# 7-GPS_GPRS.net
KiCad netlist of a schematic drawn in Altium Designer
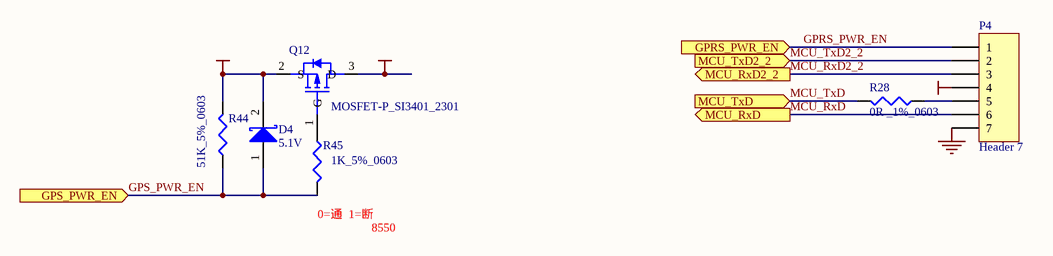
[diagram p0: 7-GPS&GPRS.SCHDOC]

(export (version "E")
  (design (tool "Eeschema 10.0.6"))
  (components
    (comp (ref "D4")
      (value "5.1V")
      (footprint "LED0805")
      (description "Schottky Diode")
      (fields (field (name "PUBLISHER") "Altium Limited"))
      (libsource (lib "Miscellaneous Devices") (part "D Schottky"))
    )
    (comp (ref "P4")
      (value "Header 7")
      (footprint "HDR1X7")
      (description "Header, 7-Pin")
      (fields (field (name "PUBLISHER") "Altium Limited"))
      (libsource (lib "Miscellaneous Connectors") (part "Header 7"))
    )
    (comp (ref "Q12")
      (value "MOSFET-P_SI3401_2301")
      (footprint "SO-G3/C2.5")
      (libsource (lib "Device") (part "MOSFET-P"))
    )
    (comp (ref "R28")
      (value "0R _1%_0603")
      (footprint "C1608-0603")
      (description "Resistor")
      (fields (field (name "PUBLISHER") "Altium Limited"))
      (libsource (lib "Miscellaneous Devices") (part "Res3"))
    )
    (comp (ref "R44")
      (value "51K_5%_0603")
      (footprint "C1608-0603")
      (description "Resistor")
      (fields (field (name "PUBLISHER") "Altium Limited"))
      (libsource (lib "Miscellaneous Devices") (part "Res3"))
    )
    (comp (ref "R45")
      (value "1K_5%_0603")
      (footprint "C1608-0603")
      (description "Resistor")
      (fields (field (name "PUBLISHER") "Altium Limited"))
      (libsource (lib "Miscellaneous Devices") (part "Res3"))
    )
  )
  (nets
    (net (code "1") (name "/GPRS_PWR_EN") (class "Default")
      (node (ref "P4") (pin "1") (pinfunction "1_1") (pintype "passive"))
    )
    (net (code "2") (name "/GPS_PWR_EN") (class "Default")
      (node (ref "D4") (pin "1") (pinfunction "A_1") (pintype "passive"))
      (node (ref "R44") (pin "1") (pinfunction "1_1") (pintype "passive"))
      (node (ref "R45") (pin "2") (pinfunction "2_2") (pintype "passive"))
    )
    (net (code "3") (name "/MCU_RxD") (class "Default")
      (node (ref "P4") (pin "6") (pinfunction "6_6") (pintype "passive"))
    )
    (net (code "4") (name "/MCU_RxD2_2") (class "Default")
      (node (ref "P4") (pin "3") (pinfunction "3_3") (pintype "passive"))
    )
    (net (code "5") (name "/MCU_TxD") (class "Default")
      (node (ref "R28") (pin "2") (pinfunction "2_2") (pintype "passive"))
    )
    (net (code "6") (name "/MCU_TxD2_2") (class "Default")
      (node (ref "P4") (pin "2") (pinfunction "2_2") (pintype "passive"))
    )
    (net (code "7") (name "GND") (class "Default")
      (node (ref "P4") (pin "7") (pinfunction "7_7") (pintype "passive"))
    )
    (net (code "8") (name "Net-(P4-Pad5)") (class "Default")
      (node (ref "P4") (pin "5") (pinfunction "5_5") (pintype "passive"))
      (node (ref "R28") (pin "1") (pinfunction "1_1") (pintype "passive"))
    )
    (net (code "9") (name "Net-(Q12-G)") (class "Default")
      (node (ref "Q12") (pin "1") (pinfunction "G_1") (pintype "passive"))
      (node (ref "R45") (pin "1") (pinfunction "1_1") (pintype "passive"))
    )
    (net (code "10") (name "VCC_2V8") (class "Default")
      (node (ref "D4") (pin "2") (pinfunction "K_2") (pintype "passive"))
      (node (ref "Q12") (pin "2") (pinfunction "S_2") (pintype "passive"))
      (node (ref "R44") (pin "2") (pinfunction "2_2") (pintype "passive"))
    )
    (net (code "11") (name "V_GPS") (class "Default")
      (node (ref "P4") (pin "4") (pinfunction "4_4") (pintype "passive"))
      (node (ref "Q12") (pin "3") (pinfunction "D_3") (pintype "passive"))
    )
  )
)
